# SWD.net
KiCad netlist of a schematic drawn in Altium Designer
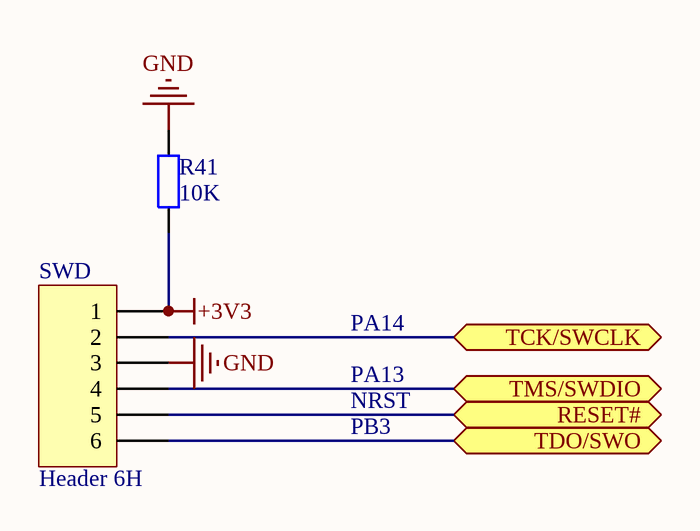
[diagram p0: SWD.SchDoc]

(export (version "E")
  (design (tool "Eeschema 10.0.6"))
  (components
    (comp (ref "R41")
      (value "10K")
      (footprint "0603_R")
      (description "Resistor")
      (fields (field (name "Comment") "R0.4W") (field (name "PUBLISHER") "Altium Limited"))
      (libsource (lib "Schematic") (part "Res 1/4 W"))
    )
    (comp (ref "SWD")
      (value "Header 6H")
      (footprint "HDR1X6")
      (description "Header, 6-Pin, Right Angle")
      (fields (field (name "PUBLISHER") "Altium Limited"))
      (libsource (lib "Miscellaneous Connectors") (part "Header 6H"))
    )
  )
  (nets
    (net (code "1") (name "+3V3") (class "Default")
      (node (ref "R41") (pin "2") (pinfunction "2_2") (pintype "passive"))
      (node (ref "SWD") (pin "1") (pinfunction "1_1") (pintype "passive"))
    )
    (net (code "2") (name "/RESET#") (class "Default")
      (node (ref "SWD") (pin "5") (pinfunction "5_5") (pintype "passive"))
    )
    (net (code "3") (name "/TCK{slash}SWCLK") (class "Default")
      (node (ref "SWD") (pin "2") (pinfunction "2_2") (pintype "passive"))
    )
    (net (code "4") (name "/TDO{slash}SWO") (class "Default")
      (node (ref "SWD") (pin "6") (pinfunction "6_6") (pintype "passive"))
    )
    (net (code "5") (name "/TMS{slash}SWDIO") (class "Default")
      (node (ref "SWD") (pin "4") (pinfunction "4_4") (pintype "passive"))
    )
    (net (code "6") (name "GND") (class "Default")
      (node (ref "R41") (pin "1") (pinfunction "1_1") (pintype "passive"))
      (node (ref "SWD") (pin "3") (pinfunction "3_3") (pintype "passive"))
    )
  )
)
